# Break_Board_Rev02.net
KiCad netlist of a schematic drawn in Altium Designer
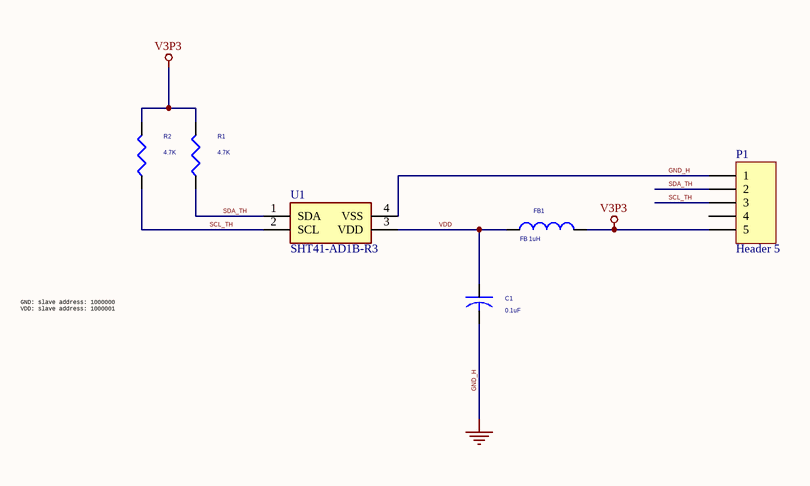
[diagram p0: Break Board_Rev02.SchDoc]

(export (version "E")
  (design (tool "Eeschema 10.0.6"))
  (components
    (comp (ref "C1")
      (value "0.1uF")
      (footprint "Break Board:0603 Capacitor")
      (fields (field (name "PART NUMBER") "1276-1011-2-ND"))
      (libsource (lib "*") (part "CAP"))
    )
    (comp (ref "FB1")
      (value "FB 1uH")
      (footprint "FD_0603(1608)_W")
      (description "FILTER CHIP 120 OHM 3A 0603")
      (fields
        (field (name "PART NUMBER") "490-3996-1-ND")
        (field (name "MANUFACTURER PART NUMBER") "MMZ2012Y152B")
      )
      (libsource (lib "*") (part "INDUCTOR"))
    )
    (comp (ref "P1")
      (value "Header 5")
      (footprint "HDR1X5")
      (description "Header, 5-Pin")
      (fields (field (name "PUBLISHER") "Altium Limited"))
      (libsource (lib "Miscellaneous Connectors") (part "Header 5"))
    )
    (comp (ref "R1")
      (value "4.7K")
      (footprint "R_0603_W")
      (fields (field (name "PART NUMBER") "P4.7KDBTR-ND"))
      (libsource (lib "*") (part "R"))
    )
    (comp (ref "R2")
      (value "4.7K")
      (footprint "R_0603_W")
      (fields (field (name "PART NUMBER") "P4.7KDBTR-ND"))
      (libsource (lib "*") (part "R"))
    )
    (comp (ref "U1")
      (value "SHT41-AD1B-R3")
      (footprint "SamacSys:SHT41AD1BR3")
      (description "Integrated Circuit")
      (fields (field (name "MOUSER PART NUMBER") "403-SHT41-AD1B-R3"))
      (libsource (lib "*") (part "SHT41-AD1B-R3"))
    )
  )
  (nets
    (net (code "1") (name "/SCL_TH") (class "Default")
      (node (ref "P1") (pin "3") (pinfunction "3_3") (pintype "passive"))
      (node (ref "R2") (pin "1") (pinfunction "1_1") (pintype "passive"))
      (node (ref "U1") (pin "2") (pinfunction "SCL_2") (pintype "passive"))
    )
    (net (code "2") (name "/SDA_TH") (class "Default")
      (node (ref "P1") (pin "2") (pinfunction "2_2") (pintype "passive"))
      (node (ref "R1") (pin "1") (pinfunction "1_1") (pintype "passive"))
      (node (ref "U1") (pin "1") (pinfunction "SDA_1") (pintype "passive"))
    )
    (net (code "3") (name "/VDD") (class "Default")
      (node (ref "C1") (pin "1") (pinfunction "1_1") (pintype "passive"))
      (node (ref "FB1") (pin "1") (pinfunction "1_1") (pintype "passive"))
      (node (ref "U1") (pin "3") (pinfunction "VDD_3") (pintype "passive"))
    )
    (net (code "4") (name "GND_POWER") (class "Default")
      (node (ref "C1") (pin "2") (pinfunction "2_2") (pintype "passive"))
      (node (ref "P1") (pin "1") (pinfunction "1_1") (pintype "passive"))
      (node (ref "U1") (pin "4") (pinfunction "VSS_4") (pintype "passive"))
    )
    (net (code "5") (name "V3P3") (class "Default")
      (node (ref "FB1") (pin "2") (pinfunction "2_2") (pintype "passive"))
      (node (ref "P1") (pin "5") (pinfunction "5_5") (pintype "passive"))
      (node (ref "R1") (pin "2") (pinfunction "2_2") (pintype "passive"))
      (node (ref "R2") (pin "2") (pinfunction "2_2") (pintype "passive"))
    )
    (net (code "6") (name "unconnected-(P1-Pad4)") (class "Default")
      (node (ref "P1") (pin "4") (pinfunction "4_4") (pintype "passive"))
    )
  )
)
